# Module.net
KiCad netlist of a schematic drawn in EAGLE
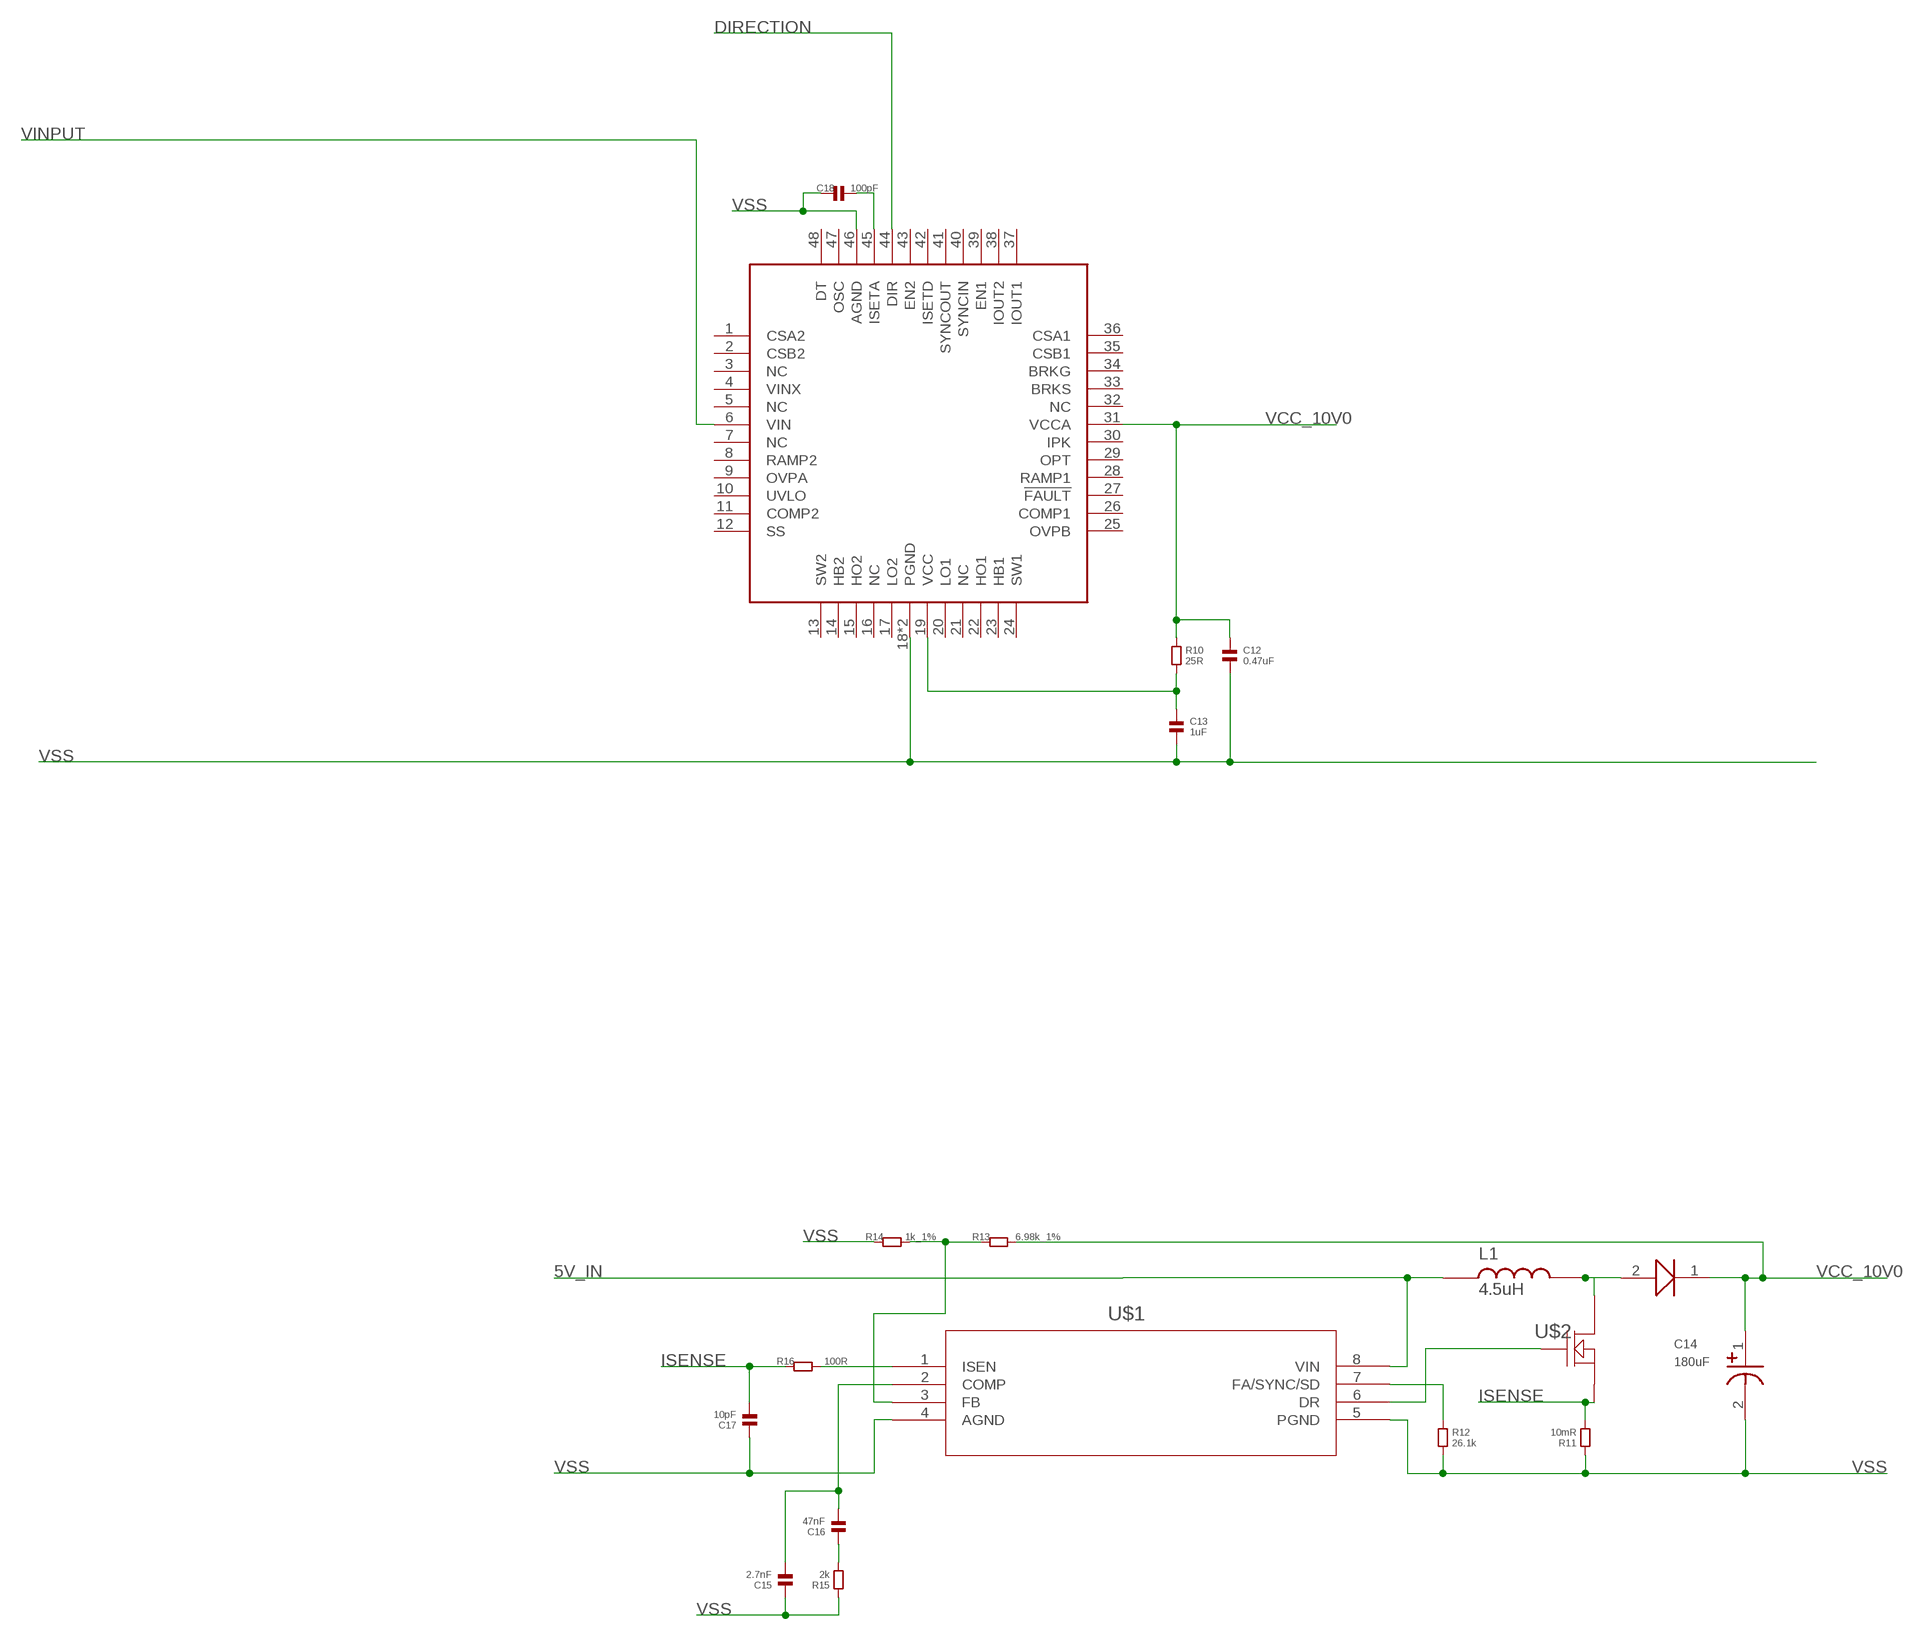
[diagram p0: schematic, sheet 1]
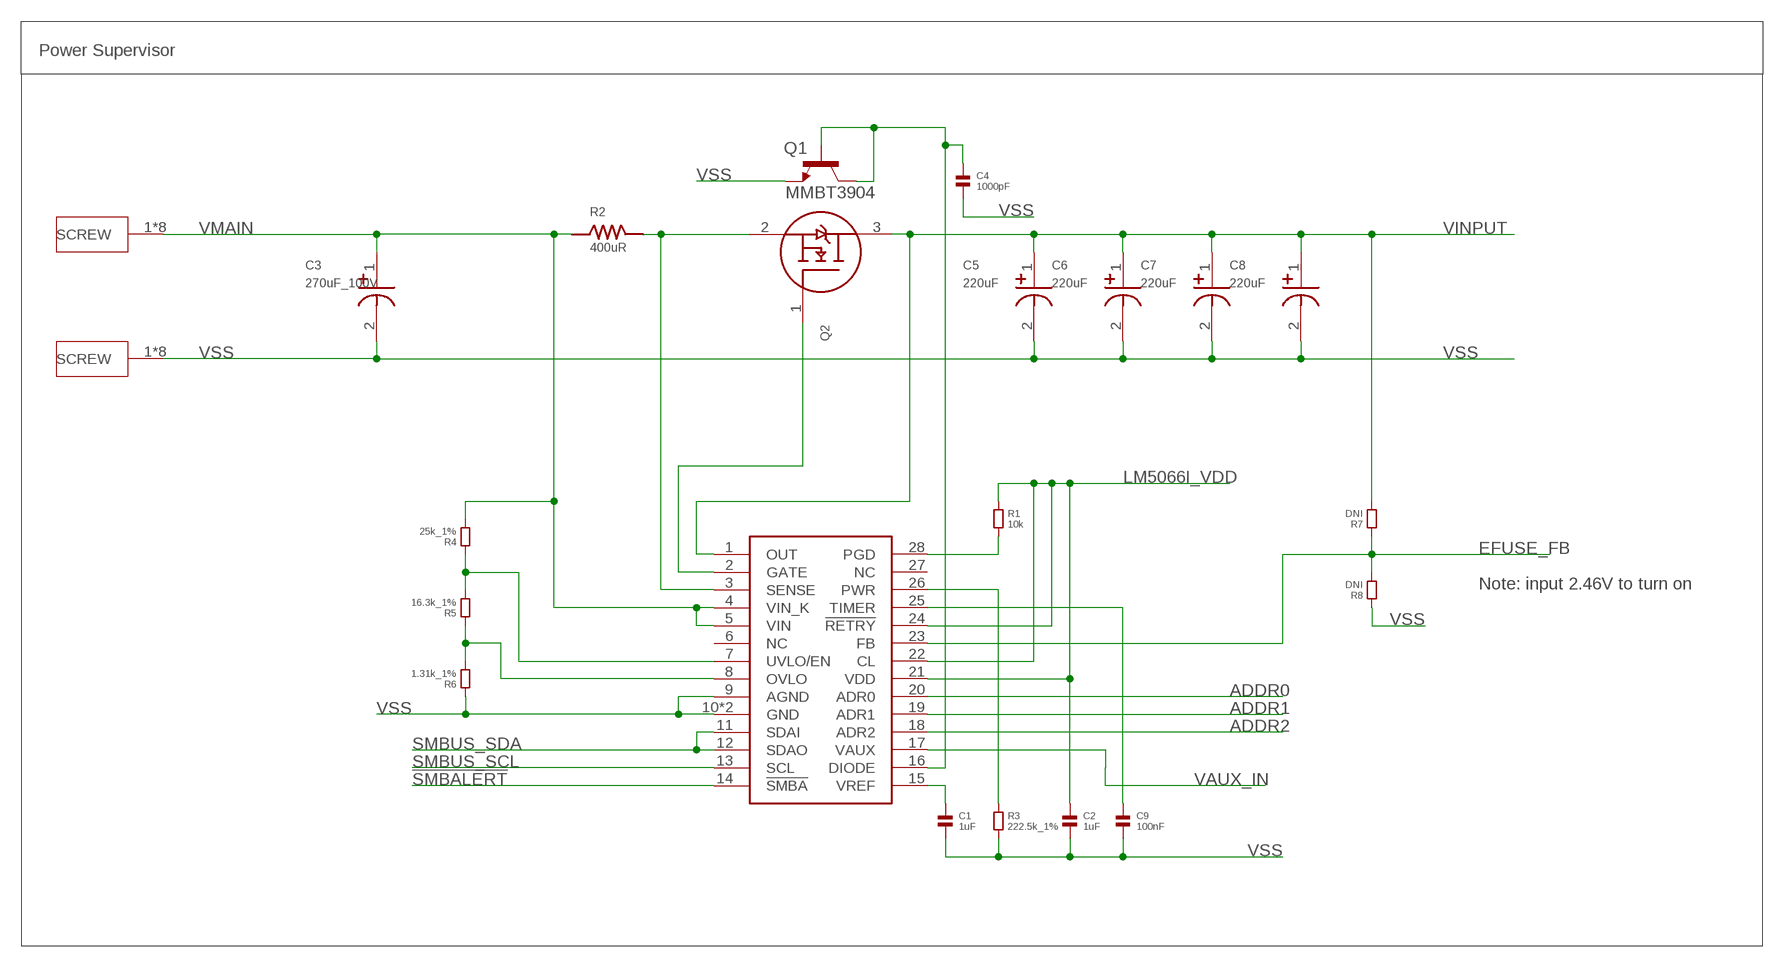
[diagram p1: schematic, sheet 3]
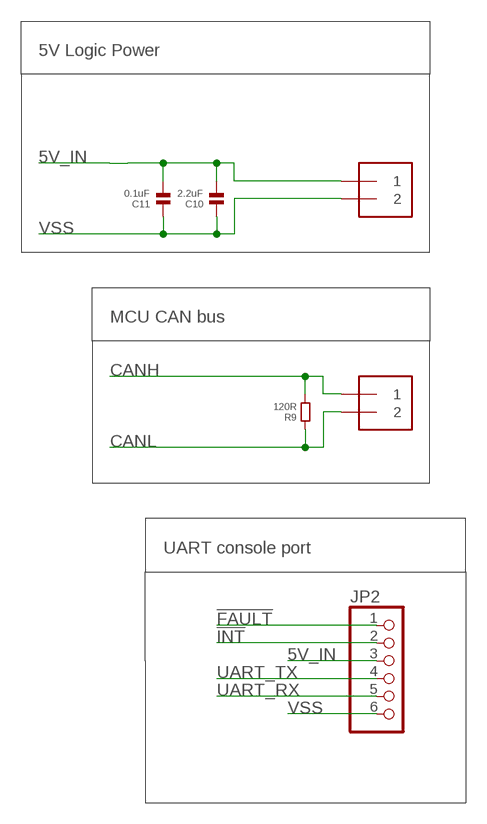
[diagram p2: schematic, sheet 4]

(export (version "E")
  (design (tool "Eeschema 10.0.6"))
  (components
    (comp (ref "C10")
      (value "2.2uF")
      (footprint "eagle-import:0603")
      (libsource (lib "eagle-import") (part "CAPACITOR.0603"))
    )
    (comp (ref "C11")
      (value "0.1uF")
      (footprint "eagle-import:0603")
      (libsource (lib "eagle-import") (part "CAPACITOR.0603"))
    )
    (comp (ref "J1")
      (value "1X2-3.5MM")
      (footprint "eagle-import:1X2-3.5MM")
      (libsource (lib "eagle-import") (part "1X2-3.5MM"))
    )
    (comp (ref "J2")
      (value "1X2-3.5MM")
      (footprint "eagle-import:1X2-3.5MM")
      (libsource (lib "eagle-import") (part "1X2-3.5MM"))
    )
    (comp (ref "JP2")
      (value "PINHD-1X6")
      (footprint "eagle-import:1X06")
      (libsource (lib "eagle-import") (part "PINHD-1X6"))
    )
    (comp (ref "R9")
      (value "120R")
      (footprint "eagle-import:0603")
      (libsource (lib "eagle-import") (part "RESISTOR.0603"))
    )
    (comp (ref "C1")
      (value "1uF")
      (footprint "eagle-import:0603")
      (libsource (lib "eagle-import") (part "CAPACITOR.0603"))
    )
    (comp (ref "C2")
      (value "1uF")
      (footprint "eagle-import:0603")
      (libsource (lib "eagle-import") (part "CAPACITOR.0603"))
    )
    (comp (ref "C3")
      (value "270uF_100V")
      (footprint "eagle-import:ALUMINUM_ELECTROLYTIC_POLARIZED-5P_12.5D_20H")
      (libsource (lib "eagle-import") (part "CAPACITOR_POLARIZED5"))
    )
    (comp (ref "C4")
      (value "1000pF")
      (footprint "eagle-import:0603")
      (libsource (lib "eagle-import") (part "CAPACITOR.0603"))
    )
    (comp (ref "C5")
      (value "220uF")
      (footprint "eagle-import:ALUMINUM_ELECTROLYTIC_POLARIZED-5P_12.5D_20H")
      (libsource (lib "eagle-import") (part "CAPACITOR_POLARIZED5"))
    )
    (comp (ref "C6")
      (value "220uF")
      (footprint "eagle-import:ALUMINUM_ELECTROLYTIC_POLARIZED-5P_12.5D_20H")
      (libsource (lib "eagle-import") (part "CAPACITOR_POLARIZED5"))
    )
    (comp (ref "C7")
      (value "220uF")
      (footprint "eagle-import:ALUMINUM_ELECTROLYTIC_POLARIZED-5P_12.5D_20H")
      (libsource (lib "eagle-import") (part "CAPACITOR_POLARIZED5"))
    )
    (comp (ref "C8")
      (value "220uF")
      (footprint "eagle-import:ALUMINUM_ELECTROLYTIC_POLARIZED-5P_12.5D_20H")
      (libsource (lib "eagle-import") (part "CAPACITOR_POLARIZED5"))
    )
    (comp (ref "C9")
      (value "100nF")
      (footprint "eagle-import:0603")
      (libsource (lib "eagle-import") (part "CAPACITOR.0603"))
    )
    (comp (ref "CN1")
      (value "WURTH_ELEKTRONIK-SCREW_TERMINAL-74650094R")
      (footprint "eagle-import:WURTH_ELEKTRONIK-SCREW_TERMINAL-74650094R")
      (libsource (lib "eagle-import") (part "WURTH_ELEKTRONIK-SCREW_TERMINAL-74650094R"))
    )
    (comp (ref "CN2")
      (value "WURTH_ELEKTRONIK-SCREW_TERMINAL-74650094R")
      (footprint "eagle-import:WURTH_ELEKTRONIK-SCREW_TERMINAL-74650094R")
      (libsource (lib "eagle-import") (part "WURTH_ELEKTRONIK-SCREW_TERMINAL-74650094R"))
    )
    (comp (ref "Q1")
      (value "MMBT3904")
      (footprint "eagle-import:SOT23")
      (fields
        (field (name "DIGIKEY_PART_NUMBER") "MMBT3904FSCT-ND")
        (field (name "MANUFACTURER") "ON Semiconductor")
        (field (name "CREATED_BY") "PCB Layout")
      )
      (libsource (lib "eagle-import") (part "MMBT3904"))
    )
    (comp (ref "Q2")
      (value "IXYS-MOSFET-IXFA72N30X3")
      (footprint "eagle-import:IXYS-MOSFET-IXFA72N30X3")
      (libsource (lib "eagle-import") (part "IXYS-MOSFET-IXFA72N30X3"))
    )
    (comp (ref "R1")
      (value "10k")
      (footprint "eagle-import:0603")
      (libsource (lib "eagle-import") (part "RESISTOR.0603"))
    )
    (comp (ref "R2")
      (value "400uR")
      (footprint "eagle-import:ROHM_SEMICONDUCTOR-SHUNT-PSR500HTQFE0L40")
      (libsource (lib "eagle-import") (part "ROHM_SEMICONDUCTOR-SHUNT-PSR500HTQFE0L40"))
    )
    (comp (ref "R3")
      (value "222.5k_1%")
      (footprint "eagle-import:0603")
      (libsource (lib "eagle-import") (part "RESISTOR.0603"))
    )
    (comp (ref "R4")
      (value "25k_1%")
      (footprint "eagle-import:0603")
      (libsource (lib "eagle-import") (part "RESISTOR.0603"))
    )
    (comp (ref "R5")
      (value "16.3k_1%")
      (footprint "eagle-import:0603")
      (libsource (lib "eagle-import") (part "RESISTOR.0603"))
    )
    (comp (ref "R6")
      (value "1.31k_1%")
      (footprint "eagle-import:0603")
      (libsource (lib "eagle-import") (part "RESISTOR.0603"))
    )
    (comp (ref "R7")
      (value "DNI")
      (footprint "eagle-import:0603")
      (libsource (lib "eagle-import") (part "RESISTOR.0603"))
    )
    (comp (ref "R8")
      (value "DNI")
      (footprint "eagle-import:0603")
      (libsource (lib "eagle-import") (part "RESISTOR.0603"))
    )
    (comp (ref "U2")
      (value "TEXAS_INSTRUMENTS-EFUSE-LM5066I")
      (footprint "eagle-import:TEXAS_INSTRUMENTS-EFUSE-LM5066I")
      (libsource (lib "eagle-import") (part "TEXAS_INSTRUMENTS-EFUSE-LM5066I"))
    )
    (comp (ref "C12")
      (value "0.47uF")
      (footprint "eagle-import:0603")
      (libsource (lib "eagle-import") (part "CAPACITOR.0603"))
    )
    (comp (ref "C13")
      (value "1uF")
      (footprint "eagle-import:0603")
      (libsource (lib "eagle-import") (part "CAPACITOR.0603"))
    )
    (comp (ref "C14")
      (value "180uF")
      (footprint "eagle-import:ALUMINUM_ELECTROLYTIC_POLARIZED-2.5P_6.3D_11H")
      (libsource (lib "eagle-import") (part "CAPACITOR_POLARIZED6"))
    )
    (comp (ref "C15")
      (value "2.7nF")
      (footprint "eagle-import:0603")
      (libsource (lib "eagle-import") (part "CAPACITOR.0603"))
    )
    (comp (ref "C16")
      (value "47nF")
      (footprint "eagle-import:0603")
      (libsource (lib "eagle-import") (part "CAPACITOR.0603"))
    )
    (comp (ref "C17")
      (value "10pF")
      (footprint "eagle-import:0603")
      (libsource (lib "eagle-import") (part "CAPACITOR.0603"))
    )
    (comp (ref "C18")
      (value "100pF")
      (footprint "eagle-import:0603")
      (libsource (lib "eagle-import") (part "CAPACITOR.0603"))
    )
    (comp (ref "D1")
      (value "DIODES_INC-DIODE-B540C-13-F")
      (footprint "eagle-import:DIODES_INCORPORATED-DIODE-B540C-13-F")
      (libsource (lib "eagle-import") (part "DIODES_INC-DIODE-B540C-13-F"))
    )
    (comp (ref "L1")
      (value "4.5uH")
      (footprint "eagle-import:BOURNS-INDUCTOR-SRR1208-4R5ML")
      (libsource (lib "eagle-import") (part "BOURNS-INDUCTOR-SRR1208-4R5ML"))
    )
    (comp (ref "R10")
      (value "25R")
      (footprint "eagle-import:0603")
      (libsource (lib "eagle-import") (part "RESISTOR.0603"))
    )
    (comp (ref "R11")
      (value "10mR")
      (footprint "eagle-import:1206")
      (libsource (lib "eagle-import") (part "RESISTOR.1206"))
    )
    (comp (ref "R12")
      (value "26.1k")
      (footprint "eagle-import:0603")
      (libsource (lib "eagle-import") (part "RESISTOR.0603"))
    )
    (comp (ref "R13")
      (value "6.98k_1%")
      (footprint "eagle-import:0603")
      (libsource (lib "eagle-import") (part "RESISTOR.0603"))
    )
    (comp (ref "R14")
      (value "1k_1%")
      (footprint "eagle-import:0603")
      (libsource (lib "eagle-import") (part "RESISTOR.0603"))
    )
    (comp (ref "R15")
      (value "2k")
      (footprint "eagle-import:0603")
      (libsource (lib "eagle-import") (part "RESISTOR.0603"))
    )
    (comp (ref "R16")
      (value "100R")
      (footprint "eagle-import:0603")
      (libsource (lib "eagle-import") (part "RESISTOR.0603"))
    )
    (comp (ref "U$1")
      (value "TEXAS_INSTRUMENTS-BOOST_CONTROLLER-LM3488_DGK_8")
      (footprint "eagle-import:TEXAS_INSTRUMENTS-BOOST_CONTROLLER-LM3488_DGK_8")
      (fields (field (name "MANUFACTURER_PART_NUMBER") "lm3488mmnopb"))
      (libsource (lib "eagle-import") (part "TEXAS_INSTRUMENTS-BOOST_CONTROLLER-LM3488_DGK_8"))
    )
    (comp (ref "U$2")
      (value "TEXAS_INSTRUMENTS-MOSFET-CSD17571Q2")
      (footprint "eagle-import:TEXAS_INSTRUMENTS-MOSFET-CSD17571Q2")
      (fields (field (name "MANUFACTURER_PART_NUMBER") "CSD17571Q2"))
      (libsource (lib "eagle-import") (part "TEXAS_INSTRUMENTS-MOSFET-CSD17571Q2"))
    )
    (comp (ref "U1")
      (value "TEXAS_INSTRUMENTS-BUCK_BOOST_CONTROLLER-LM5170")
      (footprint "eagle-import:TEXAS_INSTRUMENTS-BUCK-BOOST-CONTROLLER-LM5170")
      (libsource (lib "eagle-import") (part "TEXAS_INSTRUMENTS-BUCK_BOOST_CONTROLLER-LM5170"))
    )
  )
  (nets
    (net (code "1") (name "5V_IN") (class "Default")
      (node (ref "C10") (pin "2") (pinfunction "2_2") (pintype "bidirectional"))
      (node (ref "C11") (pin "2") (pinfunction "2_2") (pintype "bidirectional"))
      (node (ref "J1") (pin "1") (pinfunction "1_1") (pintype "passive"))
      (node (ref "JP2") (pin "3") (pinfunction "3_3") (pintype "passive"))
      (node (ref "L1") (pin "1") (pinfunction "P$1_1") (pintype "bidirectional"))
      (node (ref "U$1") (pin "8") (pinfunction "VIN_8") (pintype "power_in"))
    )
    (net (code "2") (name "ADDR0") (class "Default")
      (node (ref "U2") (pin "20") (pinfunction "ADR0_20") (pintype "bidirectional"))
    )
    (net (code "3") (name "ADDR1") (class "Default")
      (node (ref "U2") (pin "19") (pinfunction "ADR1_19") (pintype "bidirectional"))
    )
    (net (code "4") (name "ADDR2") (class "Default")
      (node (ref "U2") (pin "18") (pinfunction "ADR2_18") (pintype "bidirectional"))
    )
    (net (code "5") (name "CANH") (class "Default")
      (node (ref "J2") (pin "1") (pinfunction "1_1") (pintype "passive"))
      (node (ref "R9") (pin "2") (pinfunction "2_2") (pintype "bidirectional"))
    )
    (net (code "6") (name "CANL") (class "Default")
      (node (ref "J2") (pin "2") (pinfunction "2_2") (pintype "passive"))
      (node (ref "R9") (pin "1") (pinfunction "1_1") (pintype "bidirectional"))
    )
    (net (code "7") (name "DIRECTION") (class "Default")
      (node (ref "U1") (pin "44") (pinfunction "DIR_44") (pintype "bidirectional"))
    )
    (net (code "8") (name "EFUSE_FB") (class "Default")
      (node (ref "R7") (pin "1") (pinfunction "1_1") (pintype "bidirectional"))
      (node (ref "R8") (pin "2") (pinfunction "2_2") (pintype "bidirectional"))
      (node (ref "U2") (pin "23") (pinfunction "FB_23") (pintype "bidirectional"))
    )
    (net (code "9") (name "ISENSE") (class "Default")
      (node (ref "C17") (pin "2") (pinfunction "2_2") (pintype "bidirectional"))
      (node (ref "R11") (pin "2") (pinfunction "2_2") (pintype "bidirectional"))
      (node (ref "R16") (pin "1") (pinfunction "1_1") (pintype "bidirectional"))
      (node (ref "U$2") (pin "4") (pinfunction "SOURCE_2_4") (pintype "passive"))
    )
    (net (code "10") (name "LM5066I_VDD") (class "Default")
      (node (ref "C2") (pin "1") (pinfunction "1_1") (pintype "bidirectional"))
      (node (ref "R1") (pin "1") (pinfunction "1_1") (pintype "bidirectional"))
      (node (ref "U2") (pin "21") (pinfunction "VDD_21") (pintype "bidirectional"))
      (node (ref "U2") (pin "22") (pinfunction "CL_22") (pintype "bidirectional"))
      (node (ref "U2") (pin "24") (pinfunction "~{RETRY}_24") (pintype "bidirectional"))
    )
    (net (code "11") (name "Net-(C16-Pad1)") (class "Default")
      (node (ref "C16") (pin "1") (pinfunction "1_1") (pintype "bidirectional"))
      (node (ref "R15") (pin "2") (pinfunction "2_2") (pintype "bidirectional"))
    )
    (net (code "12") (name "Net-(D1-CATHODE)") (class "Default")
      (node (ref "D1") (pin "2") (pinfunction "CATHODE_2") (pintype "bidirectional"))
      (node (ref "L1") (pin "2") (pinfunction "P$2_2") (pintype "bidirectional"))
      (node (ref "U$2") (pin "1") (pinfunction "DRAIN_2_1") (pintype "passive"))
    )
    (net (code "13") (name "Net-(Q1-B)") (class "Default")
      (node (ref "C4") (pin "1") (pinfunction "1_1") (pintype "bidirectional"))
      (node (ref "Q1") (pin "1") (pinfunction "B_1") (pintype "passive"))
      (node (ref "Q1") (pin "3") (pinfunction "C_3") (pintype "passive"))
      (node (ref "U2") (pin "16") (pinfunction "DIODE_16") (pintype "bidirectional"))
    )
    (net (code "14") (name "Net-(Q2-GATE)") (class "Default")
      (node (ref "Q2") (pin "1") (pinfunction "GATE_1") (pintype "bidirectional"))
      (node (ref "U2") (pin "2") (pinfunction "GATE_2") (pintype "bidirectional"))
    )
    (net (code "15") (name "Net-(Q2-SOURCE)") (class "Default")
      (node (ref "Q2") (pin "2") (pinfunction "SOURCE_2") (pintype "bidirectional"))
      (node (ref "R2") (pin "2") (pinfunction "P$2_2") (pintype "bidirectional"))
      (node (ref "U2") (pin "3") (pinfunction "SENSE_3") (pintype "bidirectional"))
    )
    (net (code "16") (name "Net-(U$1-COMP)") (class "Default")
      (node (ref "C15") (pin "2") (pinfunction "2_2") (pintype "bidirectional"))
      (node (ref "C16") (pin "2") (pinfunction "2_2") (pintype "bidirectional"))
      (node (ref "U$1") (pin "2") (pinfunction "COMP_2") (pintype "passive"))
    )
    (net (code "17") (name "Net-(U$1-DR)") (class "Default")
      (node (ref "U$1") (pin "6") (pinfunction "DR_6") (pintype "output"))
      (node (ref "U$2") (pin "3") (pinfunction "GATE_3") (pintype "passive"))
    )
    (net (code "18") (name "Net-(U$1-FA{slash}SYNC{slash}SD)") (class "Default")
      (node (ref "R12") (pin "1") (pinfunction "1_1") (pintype "bidirectional"))
      (node (ref "U$1") (pin "7") (pinfunction "FA/SYNC/SD_7") (pintype "input"))
    )
    (net (code "19") (name "Net-(U$1-FB)") (class "Default")
      (node (ref "R13") (pin "1") (pinfunction "1_1") (pintype "bidirectional"))
      (node (ref "R14") (pin "2") (pinfunction "2_2") (pintype "bidirectional"))
      (node (ref "U$1") (pin "3") (pinfunction "FB_3") (pintype "input"))
    )
    (net (code "20") (name "Net-(U$1-ISEN)") (class "Default")
      (node (ref "R16") (pin "2") (pinfunction "2_2") (pintype "bidirectional"))
      (node (ref "U$1") (pin "1") (pinfunction "ISEN_1") (pintype "input"))
    )
    (net (code "21") (name "Net-(U1-ISETA)") (class "Default")
      (node (ref "C18") (pin "2") (pinfunction "2_2") (pintype "bidirectional"))
      (node (ref "U1") (pin "45") (pinfunction "ISETA_45") (pintype "bidirectional"))
    )
    (net (code "22") (name "Net-(U1-VCC)") (class "Default")
      (node (ref "C13") (pin "1") (pinfunction "1_1") (pintype "bidirectional"))
      (node (ref "R10") (pin "2") (pinfunction "2_2") (pintype "bidirectional"))
      (node (ref "U1") (pin "19") (pinfunction "VCC_19") (pintype "bidirectional"))
    )
    (net (code "23") (name "Net-(U2-OVLO)") (class "Default")
      (node (ref "R5") (pin "1") (pinfunction "1_1") (pintype "bidirectional"))
      (node (ref "R6") (pin "2") (pinfunction "2_2") (pintype "bidirectional"))
      (node (ref "U2") (pin "8") (pinfunction "OVLO_8") (pintype "bidirectional"))
    )
    (net (code "24") (name "Net-(U2-PGD)") (class "Default")
      (node (ref "R1") (pin "2") (pinfunction "2_2") (pintype "bidirectional"))
      (node (ref "U2") (pin "28") (pinfunction "PGD_28") (pintype "bidirectional"))
    )
    (net (code "25") (name "Net-(U2-PWR)") (class "Default")
      (node (ref "R3") (pin "1") (pinfunction "1_1") (pintype "bidirectional"))
      (node (ref "U2") (pin "26") (pinfunction "PWR_26") (pintype "bidirectional"))
    )
    (net (code "26") (name "Net-(U2-TIMER)") (class "Default")
      (node (ref "C9") (pin "1") (pinfunction "1_1") (pintype "bidirectional"))
      (node (ref "U2") (pin "25") (pinfunction "TIMER_25") (pintype "bidirectional"))
    )
    (net (code "27") (name "Net-(U2-UVLO{slash}EN)") (class "Default")
      (node (ref "R4") (pin "1") (pinfunction "1_1") (pintype "bidirectional"))
      (node (ref "R5") (pin "2") (pinfunction "2_2") (pintype "bidirectional"))
      (node (ref "U2") (pin "7") (pinfunction "UVLO/EN_7") (pintype "bidirectional"))
    )
    (net (code "28") (name "Net-(U2-VREF)") (class "Default")
      (node (ref "C1") (pin "1") (pinfunction "1_1") (pintype "bidirectional"))
      (node (ref "U2") (pin "15") (pinfunction "VREF_15") (pintype "bidirectional"))
    )
    (net (code "29") (name "SMBUS_SCL") (class "Default")
      (node (ref "U2") (pin "13") (pinfunction "SCL_13") (pintype "bidirectional"))
    )
    (net (code "30") (name "SMBUS_SDA") (class "Default")
      (node (ref "U2") (pin "11") (pinfunction "SDAI_11") (pintype "bidirectional"))
      (node (ref "U2") (pin "12") (pinfunction "SDAO_12") (pintype "bidirectional"))
    )
    (net (code "31") (name "UART_RX") (class "Default")
      (node (ref "JP2") (pin "5") (pinfunction "5_5") (pintype "passive"))
    )
    (net (code "32") (name "UART_TX") (class "Default")
      (node (ref "JP2") (pin "4") (pinfunction "4_4") (pintype "passive"))
    )
    (net (code "33") (name "VAUX_IN") (class "Default")
      (node (ref "U2") (pin "17") (pinfunction "VAUX_17") (pintype "bidirectional"))
    )
    (net (code "34") (name "VCC_10V0") (class "Default")
      (node (ref "C12") (pin "1") (pinfunction "1_1") (pintype "bidirectional"))
      (node (ref "C14") (pin "1") (pinfunction "+_1") (pintype "bidirectional"))
      (node (ref "D1") (pin "1") (pinfunction "ANODE_1") (pintype "bidirectional"))
      (node (ref "R10") (pin "1") (pinfunction "1_1") (pintype "bidirectional"))
      (node (ref "R13") (pin "2") (pinfunction "2_2") (pintype "bidirectional"))
      (node (ref "U1") (pin "31") (pinfunction "VCCA_31") (pintype "bidirectional"))
    )
    (net (code "35") (name "VINPUT") (class "Default")
      (node (ref "C5") (pin "1") (pinfunction "+_1") (pintype "bidirectional"))
      (node (ref "C6") (pin "1") (pinfunction "+_1") (pintype "bidirectional"))
      (node (ref "C7") (pin "1") (pinfunction "+_1") (pintype "bidirectional"))
      (node (ref "C8") (pin "1") (pinfunction "+_1") (pintype "bidirectional"))
      (node (ref "Q2") (pin "3") (pinfunction "DRAIN_3") (pintype "bidirectional"))
      (node (ref "R7") (pin "2") (pinfunction "2_2") (pintype "bidirectional"))
      (node (ref "U1") (pin "6") (pinfunction "VIN_6") (pintype "bidirectional"))
      (node (ref "U2") (pin "1") (pinfunction "OUT_1") (pintype "bidirectional"))
    )
    (net (code "36") (name "VMAIN") (class "Default")
      (node (ref "C3") (pin "1") (pinfunction "+_1") (pintype "bidirectional"))
      (node (ref "CN1") (pin "1") (pinfunction "SCREW_1") (pintype "bidirectional"))
      (node (ref "CN1") (pin "2") (pinfunction "SCREW_2") (pintype "bidirectional"))
      (node (ref "CN1") (pin "3") (pinfunction "SCREW_3") (pintype "bidirectional"))
      (node (ref "CN1") (pin "4") (pinfunction "SCREW_4") (pintype "bidirectional"))
      (node (ref "CN1") (pin "5") (pinfunction "SCREW_5") (pintype "bidirectional"))
      (node (ref "CN1") (pin "6") (pinfunction "SCREW_6") (pintype "bidirectional"))
      (node (ref "CN1") (pin "7") (pinfunction "SCREW_7") (pintype "bidirectional"))
      (node (ref "CN1") (pin "8") (pinfunction "SCREW_8") (pintype "bidirectional"))
      (node (ref "R2") (pin "1") (pinfunction "P$1_1") (pintype "bidirectional"))
      (node (ref "R4") (pin "2") (pinfunction "2_2") (pintype "bidirectional"))
      (node (ref "U2") (pin "4") (pinfunction "VIN_K_4") (pintype "bidirectional"))
      (node (ref "U2") (pin "5") (pinfunction "VIN_5") (pintype "bidirectional"))
    )
    (net (code "37") (name "VSS") (class "Default")
      (node (ref "C1") (pin "2") (pinfunction "2_2") (pintype "bidirectional"))
      (node (ref "C10") (pin "1") (pinfunction "1_1") (pintype "bidirectional"))
      (node (ref "C11") (pin "1") (pinfunction "1_1") (pintype "bidirectional"))
      (node (ref "C12") (pin "2") (pinfunction "2_2") (pintype "bidirectional"))
      (node (ref "C13") (pin "2") (pinfunction "2_2") (pintype "bidirectional"))
      (node (ref "C14") (pin "2") (pinfunction "-_2") (pintype "bidirectional"))
      (node (ref "C15") (pin "1") (pinfunction "1_1") (pintype "bidirectional"))
      (node (ref "C17") (pin "1") (pinfunction "1_1") (pintype "bidirectional"))
      (node (ref "C18") (pin "1") (pinfunction "1_1") (pintype "bidirectional"))
      (node (ref "C2") (pin "2") (pinfunction "2_2") (pintype "bidirectional"))
      (node (ref "C3") (pin "2") (pinfunction "-_2") (pintype "bidirectional"))
      (node (ref "C4") (pin "2") (pinfunction "2_2") (pintype "bidirectional"))
      (node (ref "C5") (pin "2") (pinfunction "-_2") (pintype "bidirectional"))
      (node (ref "C6") (pin "2") (pinfunction "-_2") (pintype "bidirectional"))
      (node (ref "C7") (pin "2") (pinfunction "-_2") (pintype "bidirectional"))
      (node (ref "C8") (pin "2") (pinfunction "-_2") (pintype "bidirectional"))
      (node (ref "C9") (pin "2") (pinfunction "2_2") (pintype "bidirectional"))
      (node (ref "CN2") (pin "1") (pinfunction "SCREW_1") (pintype "bidirectional"))
      (node (ref "CN2") (pin "2") (pinfunction "SCREW_2") (pintype "bidirectional"))
      (node (ref "CN2") (pin "3") (pinfunction "SCREW_3") (pintype "bidirectional"))
      (node (ref "CN2") (pin "4") (pinfunction "SCREW_4") (pintype "bidirectional"))
      (node (ref "CN2") (pin "5") (pinfunction "SCREW_5") (pintype "bidirectional"))
      (node (ref "CN2") (pin "6") (pinfunction "SCREW_6") (pintype "bidirectional"))
      (node (ref "CN2") (pin "7") (pinfunction "SCREW_7") (pintype "bidirectional"))
      (node (ref "CN2") (pin "8") (pinfunction "SCREW_8") (pintype "bidirectional"))
      (node (ref "J1") (pin "2") (pinfunction "2_2") (pintype "passive"))
      (node (ref "JP2") (pin "6") (pinfunction "6_6") (pintype "passive"))
      (node (ref "Q1") (pin "2") (pinfunction "E_2") (pintype "passive"))
      (node (ref "R11") (pin "1") (pinfunction "1_1") (pintype "bidirectional"))
      (node (ref "R12") (pin "2") (pinfunction "2_2") (pintype "bidirectional"))
      (node (ref "R14") (pin "1") (pinfunction "1_1") (pintype "bidirectional"))
      (node (ref "R15") (pin "1") (pinfunction "1_1") (pintype "bidirectional"))
      (node (ref "R3") (pin "2") (pinfunction "2_2") (pintype "bidirectional"))
      (node (ref "R6") (pin "1") (pinfunction "1_1") (pintype "bidirectional"))
      (node (ref "R8") (pin "1") (pinfunction "1_1") (pintype "bidirectional"))
      (node (ref "U$1") (pin "4") (pinfunction "AGND_4") (pintype "power_in"))
      (node (ref "U$1") (pin "5") (pinfunction "PGND_5") (pintype "power_in"))
      (node (ref "U1") (pin "18") (pinfunction "PGND_18") (pintype "bidirectional"))
      (node (ref "U1") (pin "46") (pinfunction "AGND_46") (pintype "bidirectional"))
      (node (ref "U1") (pin "49") (pinfunction "PGND_49") (pintype "bidirectional"))
      (node (ref "U2") (pin "10") (pinfunction "GND_10") (pintype "bidirectional"))
      (node (ref "U2") (pin "29") (pinfunction "GND_29") (pintype "bidirectional"))
      (node (ref "U2") (pin "9") (pinfunction "AGND_9") (pintype "bidirectional"))
    )
    (net (code "38") (name "unconnected-(U1-BRKG-Pad34)") (class "Default")
      (node (ref "U1") (pin "34") (pinfunction "BRKG_34") (pintype "bidirectional"))
    )
    (net (code "39") (name "unconnected-(U1-BRKS-Pad33)") (class "Default")
      (node (ref "U1") (pin "33") (pinfunction "BRKS_33") (pintype "bidirectional"))
    )
    (net (code "40") (name "unconnected-(U1-COMP1-Pad26)") (class "Default")
      (node (ref "U1") (pin "26") (pinfunction "COMP1_26") (pintype "bidirectional"))
    )
    (net (code "41") (name "unconnected-(U1-COMP2-Pad11)") (class "Default")
      (node (ref "U1") (pin "11") (pinfunction "COMP2_11") (pintype "bidirectional"))
    )
    (net (code "42") (name "unconnected-(U1-CSA1-Pad36)") (class "Default")
      (node (ref "U1") (pin "36") (pinfunction "CSA1_36") (pintype "bidirectional"))
    )
    (net (code "43") (name "unconnected-(U1-CSA2-Pad1)") (class "Default")
      (node (ref "U1") (pin "1") (pinfunction "CSA2_1") (pintype "bidirectional"))
    )
    (net (code "44") (name "unconnected-(U1-CSB1-Pad35)") (class "Default")
      (node (ref "U1") (pin "35") (pinfunction "CSB1_35") (pintype "bidirectional"))
    )
    (net (code "45") (name "unconnected-(U1-CSB2-Pad2)") (class "Default")
      (node (ref "U1") (pin "2") (pinfunction "CSB2_2") (pintype "bidirectional"))
    )
    (net (code "46") (name "unconnected-(U1-DT-Pad48)") (class "Default")
      (node (ref "U1") (pin "48") (pinfunction "DT_48") (pintype "bidirectional"))
    )
    (net (code "47") (name "unconnected-(U1-EN1-Pad39)") (class "Default")
      (node (ref "U1") (pin "39") (pinfunction "EN1_39") (pintype "bidirectional"))
    )
    (net (code "48") (name "unconnected-(U1-EN2-Pad43)") (class "Default")
      (node (ref "U1") (pin "43") (pinfunction "EN2_43") (pintype "bidirectional"))
    )
    (net (code "49") (name "unconnected-(U1-HB1-Pad23)") (class "Default")
      (node (ref "U1") (pin "23") (pinfunction "HB1_23") (pintype "bidirectional"))
    )
    (net (code "50") (name "unconnected-(U1-HB2-Pad14)") (class "Default")
      (node (ref "U1") (pin "14") (pinfunction "HB2_14") (pintype "bidirectional"))
    )
    (net (code "51") (name "unconnected-(U1-HO1-Pad22)") (class "Default")
      (node (ref "U1") (pin "22") (pinfunction "HO1_22") (pintype "bidirectional"))
    )
    (net (code "52") (name "unconnected-(U1-HO2-Pad15)") (class "Default")
      (node (ref "U1") (pin "15") (pinfunction "HO2_15") (pintype "bidirectional"))
    )
    (net (code "53") (name "unconnected-(U1-IOUT1-Pad37)") (class "Default")
      (node (ref "U1") (pin "37") (pinfunction "IOUT1_37") (pintype "bidirectional"))
    )
    (net (code "54") (name "unconnected-(U1-IOUT2-Pad38)") (class "Default")
      (node (ref "U1") (pin "38") (pinfunction "IOUT2_38") (pintype "bidirectional"))
    )
    (net (code "55") (name "unconnected-(U1-IPK-Pad30)") (class "Default")
      (node (ref "U1") (pin "30") (pinfunction "IPK_30") (pintype "bidirectional"))
    )
    (net (code "56") (name "unconnected-(U1-ISETD-Pad42)") (class "Default")
      (node (ref "U1") (pin "42") (pinfunction "ISETD_42") (pintype "bidirectional"))
    )
    (net (code "57") (name "unconnected-(U1-LO1-Pad20)") (class "Default")
      (node (ref "U1") (pin "20") (pinfunction "LO1_20") (pintype "bidirectional"))
    )
    (net (code "58") (name "unconnected-(U1-LO2-Pad17)") (class "Default")
      (node (ref "U1") (pin "17") (pinfunction "LO2_17") (pintype "bidirectional"))
    )
    (net (code "59") (name "unconnected-(U1-NC-Pad3)") (class "Default")
      (node (ref "U1") (pin "3") (pinfunction "NC_3") (pintype "bidirectional"))
    )
    (net (code "60") (name "unconnected-(U1-NC-Pad5)") (class "Default")
      (node (ref "U1") (pin "5") (pinfunction "NC_5") (pintype "bidirectional"))
    )
    (net (code "61") (name "unconnected-(U1-NC-Pad7)") (class "Default")
      (node (ref "U1") (pin "7") (pinfunction "NC_7") (pintype "bidirectional"))
    )
    (net (code "62") (name "unconnected-(U1-NC-Pad16)") (class "Default")
      (node (ref "U1") (pin "16") (pinfunction "NC_16") (pintype "bidirectional"))
    )
    (net (code "63") (name "unconnected-(U1-NC-Pad21)") (class "Default")
      (node (ref "U1") (pin "21") (pinfunction "NC_21") (pintype "bidirectional"))
    )
    (net (code "64") (name "unconnected-(U1-NC-Pad32)") (class "Default")
      (node (ref "U1") (pin "32") (pinfunction "NC_32") (pintype "bidirectional"))
    )
    (net (code "65") (name "unconnected-(U1-OPT-Pad29)") (class "Default")
      (node (ref "U1") (pin "29") (pinfunction "OPT_29") (pintype "bidirectional"))
    )
    (net (code "66") (name "unconnected-(U1-OSC-Pad47)") (class "Default")
      (node (ref "U1") (pin "47") (pinfunction "OSC_47") (pintype "bidirectional"))
    )
    (net (code "67") (name "unconnected-(U1-OVPA-Pad9)") (class "Default")
      (node (ref "U1") (pin "9") (pinfunction "OVPA_9") (pintype "bidirectional"))
    )
    (net (code "68") (name "unconnected-(U1-OVPB-Pad25)") (class "Default")
      (node (ref "U1") (pin "25") (pinfunction "OVPB_25") (pintype "bidirectional"))
    )
    (net (code "69") (name "unconnected-(U1-RAMP1-Pad28)") (class "Default")
      (node (ref "U1") (pin "28") (pinfunction "RAMP1_28") (pintype "bidirectional"))
    )
    (net (code "70") (name "unconnected-(U1-RAMP2-Pad8)") (class "Default")
      (node (ref "U1") (pin "8") (pinfunction "RAMP2_8") (pintype "bidirectional"))
    )
    (net (code "71") (name "unconnected-(U1-SS-Pad12)") (class "Default")
      (node (ref "U1") (pin "12") (pinfunction "SS_12") (pintype "bidirectional"))
    )
    (net (code "72") (name "unconnected-(U1-SW1-Pad24)") (class "Default")
      (node (ref "U1") (pin "24") (pinfunction "SW1_24") (pintype "bidirectional"))
    )
    (net (code "73") (name "unconnected-(U1-SW2-Pad13)") (class "Default")
      (node (ref "U1") (pin "13") (pinfunction "SW2_13") (pintype "bidirectional"))
    )
    (net (code "74") (name "unconnected-(U1-SYNCIN-Pad40)") (class "Default")
      (node (ref "U1") (pin "40") (pinfunction "SYNCIN_40") (pintype "bidirectional"))
    )
    (net (code "75") (name "unconnected-(U1-SYNCOUT-Pad41)") (class "Default")
      (node (ref "U1") (pin "41") (pinfunction "SYNCOUT_41") (pintype "bidirectional"))
    )
    (net (code "76") (name "unconnected-(U1-UVLO-Pad10)") (class "Default")
      (node (ref "U1") (pin "10") (pinfunction "UVLO_10") (pintype "bidirectional"))
    )
    (net (code "77") (name "unconnected-(U1-VINX-Pad4)") (class "Default")
      (node (ref "U1") (pin "4") (pinfunction "VINX_4") (pintype "bidirectional"))
    )
    (net (code "78") (name "unconnected-(U1-~{FAULT}-Pad27)") (class "Default")
      (node (ref "U1") (pin "27") (pinfunction "~{FAULT}_27") (pintype "bidirectional"))
    )
    (net (code "79") (name "unconnected-(U2-NC-Pad6)") (class "Default")
      (node (ref "U2") (pin "6") (pinfunction "NC_6") (pintype "bidirectional"))
    )
    (net (code "80") (name "unconnected-(U2-NC-Pad27)") (class "Default")
      (node (ref "U2") (pin "27") (pinfunction "NC_27") (pintype "bidirectional"))
    )
    (net (code "81") (name "~{FAULT}") (class "Default")
      (node (ref "JP2") (pin "1") (pinfunction "1_1") (pintype "passive"))
    )
    (net (code "82") (name "~{INT}") (class "Default")
      (node (ref "JP2") (pin "2") (pinfunction "2_2") (pintype "passive"))
    )
    (net (code "83") (name "~{SMBALERT}") (class "Default")
      (node (ref "U2") (pin "14") (pinfunction "~{SMBA}_14") (pintype "bidirectional"))
    )
  )
)
